# mixer-board3.net
KiCad netlist of a schematic drawn in EAGLE
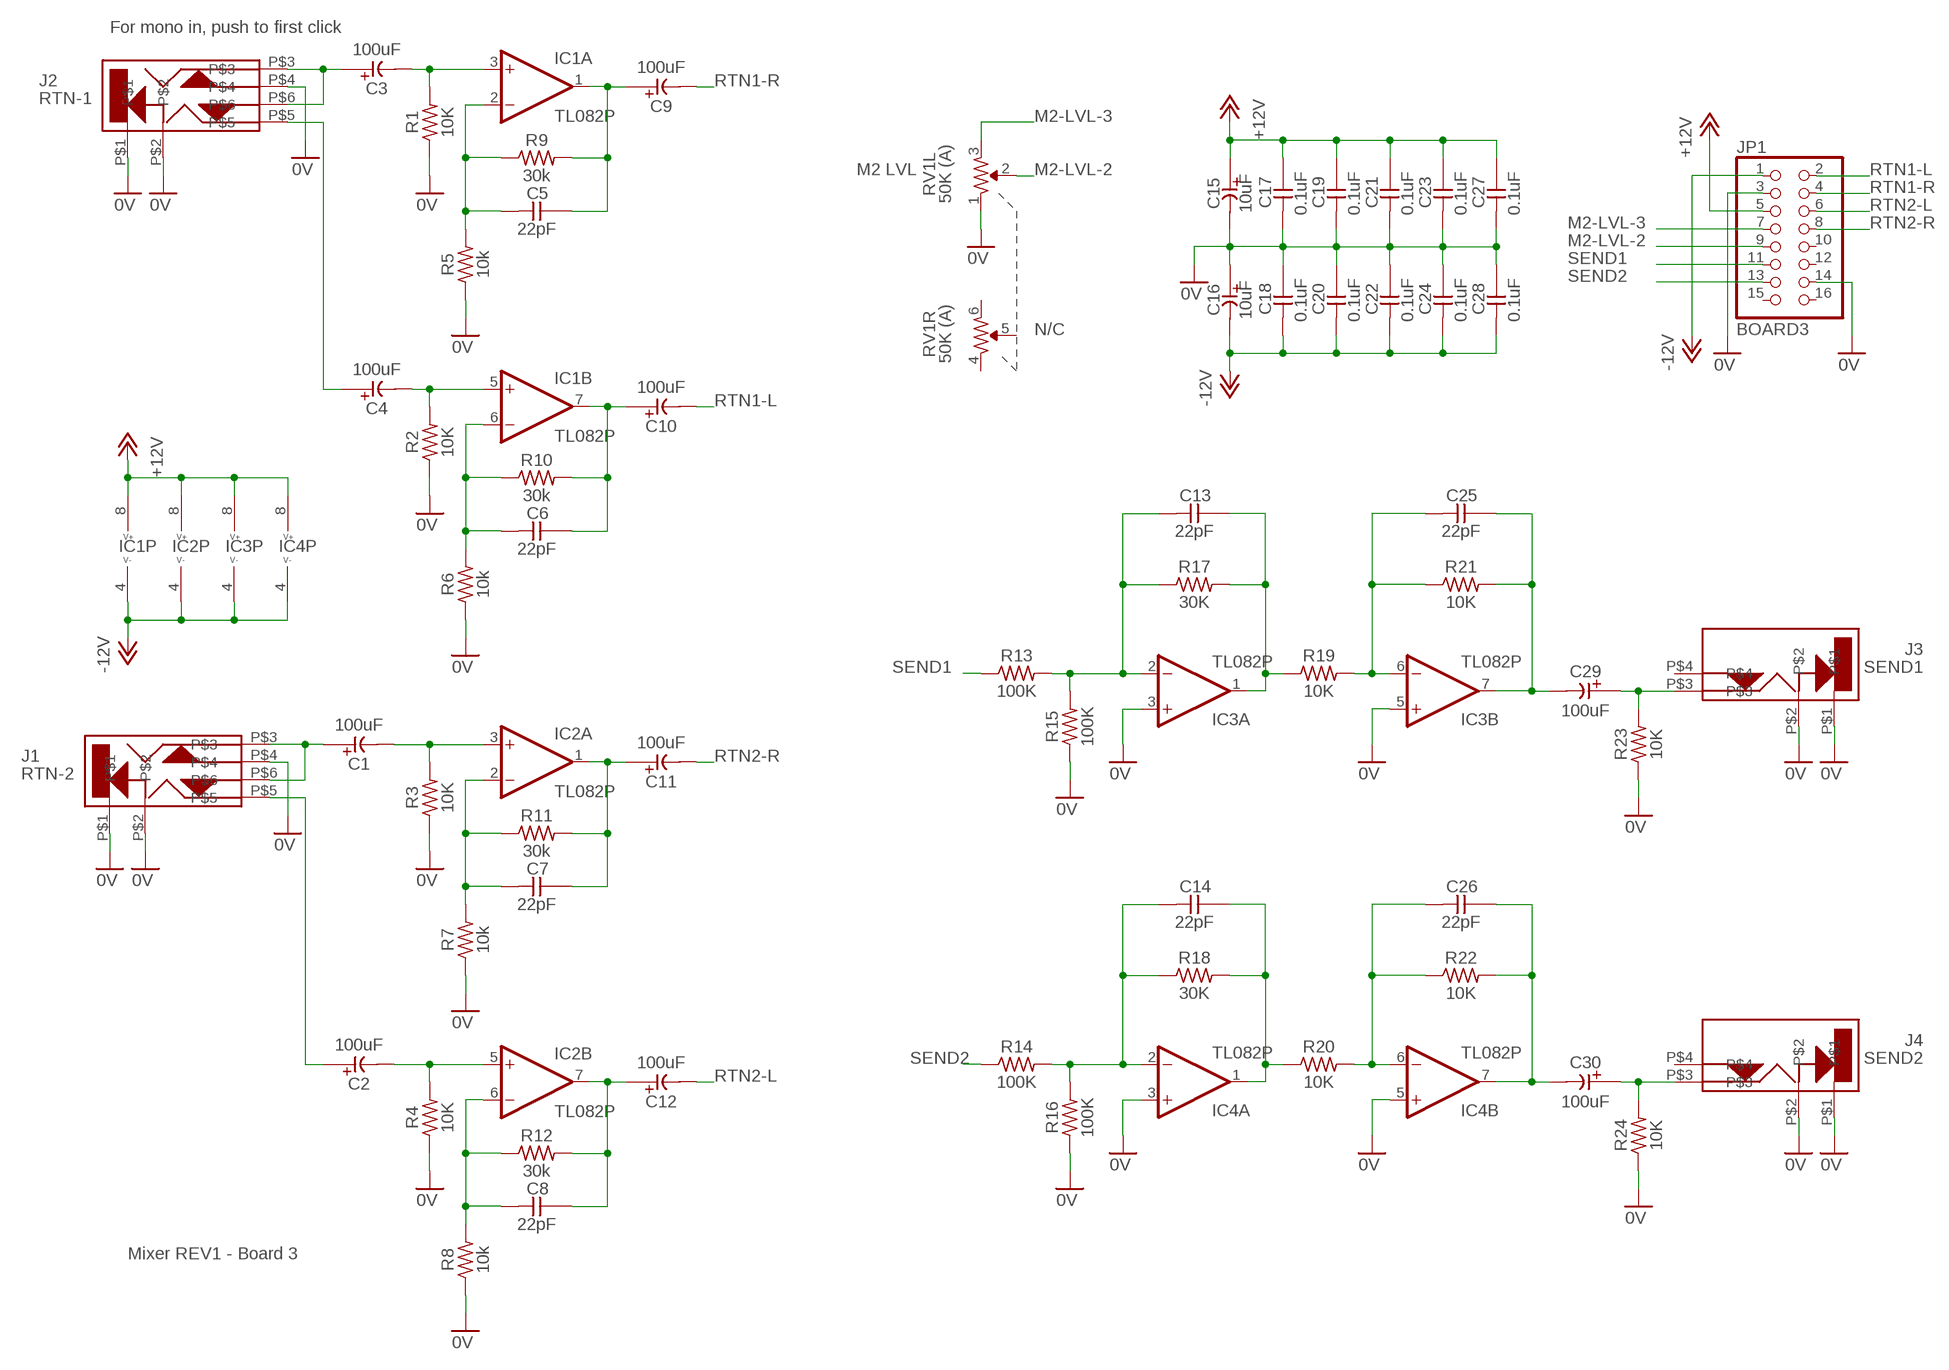
[diagram p0: schematic, sheet 1]

(export (version "E")
  (design (tool "Eeschema 10.0.6"))
  (components
    (comp (ref "C1")
      (value "100uF")
      (footprint "eagle-import:E5-8,5")
      (libsource (lib "eagle-import") (part "CE-USE5-8.5"))
    )
    (comp (ref "C2")
      (value "100uF")
      (footprint "eagle-import:E5-8,5")
      (libsource (lib "eagle-import") (part "CE-USE5-8.5"))
    )
    (comp (ref "C3")
      (value "100uF")
      (footprint "eagle-import:E5-8,5")
      (libsource (lib "eagle-import") (part "CE-USE5-8.5"))
    )
    (comp (ref "C4")
      (value "100uF")
      (footprint "eagle-import:E5-8,5")
      (libsource (lib "eagle-import") (part "CE-USE5-8.5"))
    )
    (comp (ref "C5")
      (value "22pF")
      (footprint "eagle-import:C025-024X044")
      (libsource (lib "eagle-import") (part "CC-US025-024X044"))
    )
    (comp (ref "C6")
      (value "22pF")
      (footprint "eagle-import:C025-024X044")
      (libsource (lib "eagle-import") (part "CC-US025-024X044"))
    )
    (comp (ref "C7")
      (value "22pF")
      (footprint "eagle-import:C025-024X044")
      (libsource (lib "eagle-import") (part "CC-US025-024X044"))
    )
    (comp (ref "C8")
      (value "22pF")
      (footprint "eagle-import:C025-024X044")
      (libsource (lib "eagle-import") (part "CC-US025-024X044"))
    )
    (comp (ref "C9")
      (value "100uF")
      (footprint "eagle-import:E5-8,5")
      (libsource (lib "eagle-import") (part "CE-USE5-8.5"))
    )
    (comp (ref "C10")
      (value "100uF")
      (footprint "eagle-import:E5-8,5")
      (libsource (lib "eagle-import") (part "CE-USE5-8.5"))
    )
    (comp (ref "C11")
      (value "100uF")
      (footprint "eagle-import:E5-8,5")
      (libsource (lib "eagle-import") (part "CE-USE5-8.5"))
    )
    (comp (ref "C12")
      (value "100uF")
      (footprint "eagle-import:E5-8,5")
      (libsource (lib "eagle-import") (part "CE-USE5-8.5"))
    )
    (comp (ref "C13")
      (value "22pF")
      (footprint "eagle-import:C025-024X044")
      (libsource (lib "eagle-import") (part "CC-US025-024X044"))
    )
    (comp (ref "C14")
      (value "22pF")
      (footprint "eagle-import:C025-024X044")
      (libsource (lib "eagle-import") (part "CC-US025-024X044"))
    )
    (comp (ref "C15")
      (value "10uF")
      (footprint "eagle-import:E2-5")
      (libsource (lib "eagle-import") (part "_common.v1_CE-USE2-5"))
    )
    (comp (ref "C16")
      (value "10uF")
      (footprint "eagle-import:E2-5")
      (libsource (lib "eagle-import") (part "_common.v1_CE-USE2-5"))
    )
    (comp (ref "C17")
      (value "0.1uF")
      (footprint "eagle-import:C025-024X044")
      (libsource (lib "eagle-import") (part "_common.v1_CC-US025-024X044"))
    )
    (comp (ref "C18")
      (value "0.1uF")
      (footprint "eagle-import:C025-024X044")
      (libsource (lib "eagle-import") (part "_common.v1_CC-US025-024X044"))
    )
    (comp (ref "C19")
      (value "0.1uF")
      (footprint "eagle-import:C025-024X044")
      (libsource (lib "eagle-import") (part "_common.v1_CC-US025-024X044"))
    )
    (comp (ref "C20")
      (value "0.1uF")
      (footprint "eagle-import:C025-024X044")
      (libsource (lib "eagle-import") (part "_common.v1_CC-US025-024X044"))
    )
    (comp (ref "C21")
      (value "0.1uF")
      (footprint "eagle-import:C025-024X044")
      (libsource (lib "eagle-import") (part "_common.v1_CC-US025-024X044"))
    )
    (comp (ref "C22")
      (value "0.1uF")
      (footprint "eagle-import:C025-024X044")
      (libsource (lib "eagle-import") (part "_common.v1_CC-US025-024X044"))
    )
    (comp (ref "C23")
      (value "0.1uF")
      (footprint "eagle-import:C025-024X044")
      (libsource (lib "eagle-import") (part "_common.v1_CC-US025-024X044"))
    )
    (comp (ref "C24")
      (value "0.1uF")
      (footprint "eagle-import:C025-024X044")
      (libsource (lib "eagle-import") (part "_common.v1_CC-US025-024X044"))
    )
    (comp (ref "C25")
      (value "22pF")
      (footprint "eagle-import:C025-024X044")
      (libsource (lib "eagle-import") (part "CC-US025-024X044"))
    )
    (comp (ref "C26")
      (value "22pF")
      (footprint "eagle-import:C025-024X044")
      (libsource (lib "eagle-import") (part "CC-US025-024X044"))
    )
    (comp (ref "C27")
      (value "0.1uF")
      (footprint "eagle-import:C025-024X044")
      (libsource (lib "eagle-import") (part "_common.v1_CC-US025-024X044"))
    )
    (comp (ref "C28")
      (value "0.1uF")
      (footprint "eagle-import:C025-024X044")
      (libsource (lib "eagle-import") (part "_common.v1_CC-US025-024X044"))
    )
    (comp (ref "C29")
      (value "100uF")
      (footprint "eagle-import:E5-8,5")
      (libsource (lib "eagle-import") (part "CE-USE5-8.5"))
    )
    (comp (ref "C30")
      (value "100uF")
      (footprint "eagle-import:E5-8,5")
      (libsource (lib "eagle-import") (part "CE-USE5-8.5"))
    )
    (comp (ref "IC1")
      (value "TL082P")
      (footprint "eagle-import:DIL08")
      (libsource (lib "eagle-import") (part "TL082P"))
    )
    (comp (ref "IC2")
      (value "TL082P")
      (footprint "eagle-import:DIL08")
      (libsource (lib "eagle-import") (part "TL082P"))
    )
    (comp (ref "IC3")
      (value "TL082P")
      (footprint "eagle-import:DIL08")
      (libsource (lib "eagle-import") (part "TL082P"))
    )
    (comp (ref "IC4")
      (value "TL082P")
      (footprint "eagle-import:DIL08")
      (libsource (lib "eagle-import") (part "TL082P"))
    )
    (comp (ref "J1")
      (value "RTN-2")
      (footprint "eagle-import:NYS216-U")
      (libsource (lib "eagle-import") (part "NYS216-U"))
    )
    (comp (ref "J2")
      (value "RTN-1")
      (footprint "eagle-import:NYS216-U")
      (libsource (lib "eagle-import") (part "NYS216-U"))
    )
    (comp (ref "J3")
      (value "SEND1")
      (footprint "eagle-import:NYS2162-U")
      (libsource (lib "eagle-import") (part "NYS2162-U"))
    )
    (comp (ref "J4")
      (value "SEND2")
      (footprint "eagle-import:NYS2162-U")
      (libsource (lib "eagle-import") (part "NYS2162-U"))
    )
    (comp (ref "JP1")
      (value "BOARD3")
      (footprint "eagle-import:2X08")
      (libsource (lib "eagle-import") (part "PINHD-2X8"))
    )
    (comp (ref "R1")
      (value "10K")
      (footprint "eagle-import:0207_7")
      (libsource (lib "eagle-import") (part "R"))
    )
    (comp (ref "R2")
      (value "10K")
      (footprint "eagle-import:0207_7")
      (libsource (lib "eagle-import") (part "R"))
    )
    (comp (ref "R3")
      (value "10K")
      (footprint "eagle-import:0207_7")
      (libsource (lib "eagle-import") (part "R"))
    )
    (comp (ref "R4")
      (value "10K")
      (footprint "eagle-import:0207_7")
      (libsource (lib "eagle-import") (part "R"))
    )
    (comp (ref "R5")
      (value "10k")
      (footprint "eagle-import:0207_7")
      (libsource (lib "eagle-import") (part "R"))
    )
    (comp (ref "R6")
      (value "10k")
      (footprint "eagle-import:0207_7")
      (libsource (lib "eagle-import") (part "R"))
    )
    (comp (ref "R7")
      (value "10k")
      (footprint "eagle-import:0207_7")
      (libsource (lib "eagle-import") (part "R"))
    )
    (comp (ref "R8")
      (value "10k")
      (footprint "eagle-import:0207_7")
      (libsource (lib "eagle-import") (part "R"))
    )
    (comp (ref "R9")
      (value "30k")
      (footprint "eagle-import:0207_7")
      (libsource (lib "eagle-import") (part "R"))
    )
    (comp (ref "R10")
      (value "30k")
      (footprint "eagle-import:0207_7")
      (libsource (lib "eagle-import") (part "R"))
    )
    (comp (ref "R11")
      (value "30k")
      (footprint "eagle-import:0207_7")
      (libsource (lib "eagle-import") (part "R"))
    )
    (comp (ref "R12")
      (value "30k")
      (footprint "eagle-import:0207_7")
      (libsource (lib "eagle-import") (part "R"))
    )
    (comp (ref "R13")
      (value "100K")
      (footprint "eagle-import:0207_7")
      (libsource (lib "eagle-import") (part "R"))
    )
    (comp (ref "R14")
      (value "100K")
      (footprint "eagle-import:0207_7")
      (libsource (lib "eagle-import") (part "R"))
    )
    (comp (ref "R15")
      (value "100K")
      (footprint "eagle-import:0207_7")
      (libsource (lib "eagle-import") (part "R"))
    )
    (comp (ref "R16")
      (value "100K")
      (footprint "eagle-import:0207_7")
      (libsource (lib "eagle-import") (part "R"))
    )
    (comp (ref "R17")
      (value "30K")
      (footprint "eagle-import:0207_7")
      (libsource (lib "eagle-import") (part "R"))
    )
    (comp (ref "R18")
      (value "30K")
      (footprint "eagle-import:0207_7")
      (libsource (lib "eagle-import") (part "R"))
    )
    (comp (ref "R19")
      (value "10K")
      (footprint "eagle-import:0207_7")
      (libsource (lib "eagle-import") (part "R"))
    )
    (comp (ref "R20")
      (value "10K")
      (footprint "eagle-import:0207_7")
      (libsource (lib "eagle-import") (part "R"))
    )
    (comp (ref "R21")
      (value "10K")
      (footprint "eagle-import:0207_7")
      (libsource (lib "eagle-import") (part "R"))
    )
    (comp (ref "R22")
      (value "10K")
      (footprint "eagle-import:0207_7")
      (libsource (lib "eagle-import") (part "R"))
    )
    (comp (ref "R23")
      (value "10K")
      (footprint "eagle-import:0207_7")
      (libsource (lib "eagle-import") (part "R"))
    )
    (comp (ref "R24")
      (value "10K")
      (footprint "eagle-import:0207_7")
      (libsource (lib "eagle-import") (part "R"))
    )
    (comp (ref "RV1")
      (value "50K (A)")
      (footprint "eagle-import:_COMMON_3RP_1610G")
      (libsource (lib "eagle-import") (part "R-VAR-ST"))
    )
  )
  (nets
    (net (code "1") (name "+12V") (class "Default")
      (node (ref "C15") (pin "+") (pinfunction "+_+") (pintype "passive"))
      (node (ref "C17") (pin "1") (pinfunction "1_1") (pintype "passive"))
      (node (ref "C19") (pin "1") (pinfunction "1_1") (pintype "passive"))
      (node (ref "C21") (pin "1") (pinfunction "1_1") (pintype "passive"))
      (node (ref "C23") (pin "1") (pinfunction "1_1") (pintype "passive"))
      (node (ref "C27") (pin "1") (pinfunction "1_1") (pintype "passive"))
      (node (ref "IC1") (pin "8") (pinfunction "V+_8") (pintype "power_in"))
      (node (ref "IC2") (pin "8") (pinfunction "V+_8") (pintype "power_in"))
      (node (ref "IC3") (pin "8") (pinfunction "V+_8") (pintype "power_in"))
      (node (ref "IC4") (pin "8") (pinfunction "V+_8") (pintype "power_in"))
      (node (ref "JP1") (pin "5") (pinfunction "5_5") (pintype "passive"))
    )
    (net (code "2") (name "-12V") (class "Default")
      (node (ref "C16") (pin "-") (pinfunction "-_-") (pintype "passive"))
      (node (ref "C18") (pin "2") (pinfunction "2_2") (pintype "passive"))
      (node (ref "C20") (pin "2") (pinfunction "2_2") (pintype "passive"))
      (node (ref "C22") (pin "2") (pinfunction "2_2") (pintype "passive"))
      (node (ref "C24") (pin "2") (pinfunction "2_2") (pintype "passive"))
      (node (ref "C28") (pin "2") (pinfunction "2_2") (pintype "passive"))
      (node (ref "IC1") (pin "4") (pinfunction "V-_4") (pintype "power_in"))
      (node (ref "IC2") (pin "4") (pinfunction "V-_4") (pintype "power_in"))
      (node (ref "IC3") (pin "4") (pinfunction "V-_4") (pintype "power_in"))
      (node (ref "IC4") (pin "4") (pinfunction "V-_4") (pintype "power_in"))
      (node (ref "JP1") (pin "1") (pinfunction "1_1") (pintype "passive"))
    )
    (net (code "3") (name "/M2-LVL-2") (class "Default")
      (node (ref "JP1") (pin "9") (pinfunction "9_9") (pintype "passive"))
      (node (ref "RV1") (pin "2") (pinfunction "2_2") (pintype "passive"))
    )
    (net (code "4") (name "/M2-LVL-3") (class "Default")
      (node (ref "JP1") (pin "7") (pinfunction "7_7") (pintype "passive"))
      (node (ref "RV1") (pin "3") (pinfunction "3_3") (pintype "passive"))
    )
    (net (code "5") (name "/RTN1-L") (class "Default")
      (node (ref "C10") (pin "-") (pinfunction "-_-") (pintype "passive"))
      (node (ref "JP1") (pin "2") (pinfunction "2_2") (pintype "passive"))
    )
    (net (code "6") (name "/RTN1-R") (class "Default")
      (node (ref "C9") (pin "-") (pinfunction "-_-") (pintype "passive"))
      (node (ref "JP1") (pin "4") (pinfunction "4_4") (pintype "passive"))
    )
    (net (code "7") (name "/RTN2-L") (class "Default")
      (node (ref "C12") (pin "-") (pinfunction "-_-") (pintype "passive"))
      (node (ref "JP1") (pin "6") (pinfunction "6_6") (pintype "passive"))
    )
    (net (code "8") (name "/RTN2-R") (class "Default")
      (node (ref "C11") (pin "-") (pinfunction "-_-") (pintype "passive"))
      (node (ref "JP1") (pin "8") (pinfunction "8_8") (pintype "passive"))
    )
    (net (code "9") (name "/SEND1") (class "Default")
      (node (ref "JP1") (pin "11") (pinfunction "11_11") (pintype "passive"))
      (node (ref "R13") (pin "1") (pinfunction "1_1") (pintype "passive"))
    )
    (net (code "10") (name "/SEND2") (class "Default")
      (node (ref "JP1") (pin "13") (pinfunction "13_13") (pintype "passive"))
      (node (ref "R14") (pin "1") (pinfunction "1_1") (pintype "passive"))
    )
    (net (code "11") (name "0V") (class "Default")
      (node (ref "C15") (pin "-") (pinfunction "-_-") (pintype "passive"))
      (node (ref "C16") (pin "+") (pinfunction "+_+") (pintype "passive"))
      (node (ref "C17") (pin "2") (pinfunction "2_2") (pintype "passive"))
      (node (ref "C18") (pin "1") (pinfunction "1_1") (pintype "passive"))
      (node (ref "C19") (pin "2") (pinfunction "2_2") (pintype "passive"))
      (node (ref "C20") (pin "1") (pinfunction "1_1") (pintype "passive"))
      (node (ref "C21") (pin "2") (pinfunction "2_2") (pintype "passive"))
      (node (ref "C22") (pin "1") (pinfunction "1_1") (pintype "passive"))
      (node (ref "C23") (pin "2") (pinfunction "2_2") (pintype "passive"))
      (node (ref "C24") (pin "1") (pinfunction "1_1") (pintype "passive"))
      (node (ref "C27") (pin "2") (pinfunction "2_2") (pintype "passive"))
      (node (ref "C28") (pin "1") (pinfunction "1_1") (pintype "passive"))
      (node (ref "IC3") (pin "3") (pinfunction "+IN_3") (pintype "input"))
      (node (ref "IC3") (pin "5") (pinfunction "+IN_5") (pintype "input"))
      (node (ref "IC4") (pin "3") (pinfunction "+IN_3") (pintype "input"))
      (node (ref "IC4") (pin "5") (pinfunction "+IN_5") (pintype "input"))
      (node (ref "J1") (pin "P$1") (pinfunction "P$1_P$1") (pintype "bidirectional"))
      (node (ref "J1") (pin "P$2") (pinfunction "P$2_P$2") (pintype "bidirectional"))
      (node (ref "J1") (pin "P$4") (pinfunction "P$4_P$4") (pintype "bidirectional"))
      (node (ref "J2") (pin "P$1") (pinfunction "P$1_P$1") (pintype "bidirectional"))
      (node (ref "J2") (pin "P$2") (pinfunction "P$2_P$2") (pintype "bidirectional"))
      (node (ref "J2") (pin "P$4") (pinfunction "P$4_P$4") (pintype "bidirectional"))
      (node (ref "J3") (pin "P$1") (pinfunction "P$1_P$1") (pintype "bidirectional"))
      (node (ref "J3") (pin "P$2") (pinfunction "P$2_P$2") (pintype "bidirectional"))
      (node (ref "J4") (pin "P$1") (pinfunction "P$1_P$1") (pintype "bidirectional"))
      (node (ref "J4") (pin "P$2") (pinfunction "P$2_P$2") (pintype "bidirectional"))
      (node (ref "JP1") (pin "14") (pinfunction "14_14") (pintype "passive"))
      (node (ref "JP1") (pin "3") (pinfunction "3_3") (pintype "passive"))
      (node (ref "R1") (pin "1") (pinfunction "1_1") (pintype "passive"))
      (node (ref "R15") (pin "1") (pinfunction "1_1") (pintype "passive"))
      (node (ref "R16") (pin "1") (pinfunction "1_1") (pintype "passive"))
      (node (ref "R2") (pin "1") (pinfunction "1_1") (pintype "passive"))
      (node (ref "R23") (pin "1") (pinfunction "1_1") (pintype "passive"))
      (node (ref "R24") (pin "1") (pinfunction "1_1") (pintype "passive"))
      (node (ref "R3") (pin "1") (pinfunction "1_1") (pintype "passive"))
      (node (ref "R4") (pin "1") (pinfunction "1_1") (pintype "passive"))
      (node (ref "R5") (pin "1") (pinfunction "1_1") (pintype "passive"))
      (node (ref "R6") (pin "1") (pinfunction "1_1") (pintype "passive"))
      (node (ref "R7") (pin "1") (pinfunction "1_1") (pintype "passive"))
      (node (ref "R8") (pin "1") (pinfunction "1_1") (pintype "passive"))
      (node (ref "RV1") (pin "1") (pinfunction "1_1") (pintype "passive"))
    )
    (net (code "12") (name "Net-(C1-Pad+)") (class "Default")
      (node (ref "C1") (pin "+") (pinfunction "+_+") (pintype "passive"))
      (node (ref "J1") (pin "P$3") (pinfunction "P$3_P$3") (pintype "bidirectional"))
      (node (ref "J1") (pin "P$6") (pinfunction "P$6_P$6") (pintype "bidirectional"))
    )
    (net (code "13") (name "Net-(C2-Pad+)") (class "Default")
      (node (ref "C2") (pin "+") (pinfunction "+_+") (pintype "passive"))
      (node (ref "J1") (pin "P$5") (pinfunction "P$5_P$5") (pintype "bidirectional"))
    )
    (net (code "14") (name "Net-(C3-Pad+)") (class "Default")
      (node (ref "C3") (pin "+") (pinfunction "+_+") (pintype "passive"))
      (node (ref "J2") (pin "P$3") (pinfunction "P$3_P$3") (pintype "bidirectional"))
      (node (ref "J2") (pin "P$6") (pinfunction "P$6_P$6") (pintype "bidirectional"))
    )
    (net (code "15") (name "Net-(C4-Pad+)") (class "Default")
      (node (ref "C4") (pin "+") (pinfunction "+_+") (pintype "passive"))
      (node (ref "J2") (pin "P$5") (pinfunction "P$5_P$5") (pintype "bidirectional"))
    )
    (net (code "16") (name "Net-(C29-Pad+)") (class "Default")
      (node (ref "C29") (pin "+") (pinfunction "+_+") (pintype "passive"))
      (node (ref "J3") (pin "P$3") (pinfunction "P$3_P$3") (pintype "bidirectional"))
      (node (ref "R23") (pin "2") (pinfunction "2_2") (pintype "passive"))
    )
    (net (code "17") (name "Net-(C30-Pad+)") (class "Default")
      (node (ref "C30") (pin "+") (pinfunction "+_+") (pintype "passive"))
      (node (ref "J4") (pin "P$3") (pinfunction "P$3_P$3") (pintype "bidirectional"))
      (node (ref "R24") (pin "2") (pinfunction "2_2") (pintype "passive"))
    )
    (net (code "18") (name "Net-(IC1A-+IN)") (class "Default")
      (node (ref "C3") (pin "-") (pinfunction "-_-") (pintype "passive"))
      (node (ref "IC1") (pin "3") (pinfunction "+IN_3") (pintype "input"))
      (node (ref "R1") (pin "2") (pinfunction "2_2") (pintype "passive"))
    )
    (net (code "19") (name "Net-(IC1A--IN)") (class "Default")
      (node (ref "C5") (pin "2") (pinfunction "2_2") (pintype "passive"))
      (node (ref "IC1") (pin "2") (pinfunction "-IN_2") (pintype "input"))
      (node (ref "R5") (pin "2") (pinfunction "2_2") (pintype "passive"))
      (node (ref "R9") (pin "1") (pinfunction "1_1") (pintype "passive"))
    )
    (net (code "20") (name "Net-(IC1A-OUT)") (class "Default")
      (node (ref "C5") (pin "1") (pinfunction "1_1") (pintype "passive"))
      (node (ref "C9") (pin "+") (pinfunction "+_+") (pintype "passive"))
      (node (ref "IC1") (pin "1") (pinfunction "OUT_1") (pintype "output"))
      (node (ref "R9") (pin "2") (pinfunction "2_2") (pintype "passive"))
    )
    (net (code "21") (name "Net-(IC1B-+IN)") (class "Default")
      (node (ref "C4") (pin "-") (pinfunction "-_-") (pintype "passive"))
      (node (ref "IC1") (pin "5") (pinfunction "+IN_5") (pintype "input"))
      (node (ref "R2") (pin "2") (pinfunction "2_2") (pintype "passive"))
    )
    (net (code "22") (name "Net-(IC1B--IN)") (class "Default")
      (node (ref "C6") (pin "2") (pinfunction "2_2") (pintype "passive"))
      (node (ref "IC1") (pin "6") (pinfunction "-IN_6") (pintype "input"))
      (node (ref "R10") (pin "1") (pinfunction "1_1") (pintype "passive"))
      (node (ref "R6") (pin "2") (pinfunction "2_2") (pintype "passive"))
    )
    (net (code "23") (name "Net-(IC1B-OUT)") (class "Default")
      (node (ref "C10") (pin "+") (pinfunction "+_+") (pintype "passive"))
      (node (ref "C6") (pin "1") (pinfunction "1_1") (pintype "passive"))
      (node (ref "IC1") (pin "7") (pinfunction "OUT_7") (pintype "output"))
      (node (ref "R10") (pin "2") (pinfunction "2_2") (pintype "passive"))
    )
    (net (code "24") (name "Net-(IC2A-+IN)") (class "Default")
      (node (ref "C1") (pin "-") (pinfunction "-_-") (pintype "passive"))
      (node (ref "IC2") (pin "3") (pinfunction "+IN_3") (pintype "input"))
      (node (ref "R3") (pin "2") (pinfunction "2_2") (pintype "passive"))
    )
    (net (code "25") (name "Net-(IC2A--IN)") (class "Default")
      (node (ref "C7") (pin "2") (pinfunction "2_2") (pintype "passive"))
      (node (ref "IC2") (pin "2") (pinfunction "-IN_2") (pintype "input"))
      (node (ref "R11") (pin "1") (pinfunction "1_1") (pintype "passive"))
      (node (ref "R7") (pin "2") (pinfunction "2_2") (pintype "passive"))
    )
    (net (code "26") (name "Net-(IC2A-OUT)") (class "Default")
      (node (ref "C11") (pin "+") (pinfunction "+_+") (pintype "passive"))
      (node (ref "C7") (pin "1") (pinfunction "1_1") (pintype "passive"))
      (node (ref "IC2") (pin "1") (pinfunction "OUT_1") (pintype "output"))
      (node (ref "R11") (pin "2") (pinfunction "2_2") (pintype "passive"))
    )
    (net (code "27") (name "Net-(IC2B-+IN)") (class "Default")
      (node (ref "C2") (pin "-") (pinfunction "-_-") (pintype "passive"))
      (node (ref "IC2") (pin "5") (pinfunction "+IN_5") (pintype "input"))
      (node (ref "R4") (pin "2") (pinfunction "2_2") (pintype "passive"))
    )
    (net (code "28") (name "Net-(IC2B--IN)") (class "Default")
      (node (ref "C8") (pin "2") (pinfunction "2_2") (pintype "passive"))
      (node (ref "IC2") (pin "6") (pinfunction "-IN_6") (pintype "input"))
      (node (ref "R12") (pin "1") (pinfunction "1_1") (pintype "passive"))
      (node (ref "R8") (pin "2") (pinfunction "2_2") (pintype "passive"))
    )
    (net (code "29") (name "Net-(IC2B-OUT)") (class "Default")
      (node (ref "C12") (pin "+") (pinfunction "+_+") (pintype "passive"))
      (node (ref "C8") (pin "1") (pinfunction "1_1") (pintype "passive"))
      (node (ref "IC2") (pin "7") (pinfunction "OUT_7") (pintype "output"))
      (node (ref "R12") (pin "2") (pinfunction "2_2") (pintype "passive"))
    )
    (net (code "30") (name "Net-(IC3A--IN)") (class "Default")
      (node (ref "C13") (pin "2") (pinfunction "2_2") (pintype "passive"))
      (node (ref "IC3") (pin "2") (pinfunction "-IN_2") (pintype "input"))
      (node (ref "R13") (pin "2") (pinfunction "2_2") (pintype "passive"))
      (node (ref "R15") (pin "2") (pinfunction "2_2") (pintype "passive"))
      (node (ref "R17") (pin "1") (pinfunction "1_1") (pintype "passive"))
    )
    (net (code "31") (name "Net-(IC3A-OUT)") (class "Default")
      (node (ref "C13") (pin "1") (pinfunction "1_1") (pintype "passive"))
      (node (ref "IC3") (pin "1") (pinfunction "OUT_1") (pintype "output"))
      (node (ref "R17") (pin "2") (pinfunction "2_2") (pintype "passive"))
      (node (ref "R19") (pin "1") (pinfunction "1_1") (pintype "passive"))
    )
    (net (code "32") (name "Net-(IC3B--IN)") (class "Default")
      (node (ref "C25") (pin "2") (pinfunction "2_2") (pintype "passive"))
      (node (ref "IC3") (pin "6") (pinfunction "-IN_6") (pintype "input"))
      (node (ref "R19") (pin "2") (pinfunction "2_2") (pintype "passive"))
      (node (ref "R21") (pin "1") (pinfunction "1_1") (pintype "passive"))
    )
    (net (code "33") (name "Net-(IC3B-OUT)") (class "Default")
      (node (ref "C25") (pin "1") (pinfunction "1_1") (pintype "passive"))
      (node (ref "C29") (pin "-") (pinfunction "-_-") (pintype "passive"))
      (node (ref "IC3") (pin "7") (pinfunction "OUT_7") (pintype "output"))
      (node (ref "R21") (pin "2") (pinfunction "2_2") (pintype "passive"))
    )
    (net (code "34") (name "Net-(IC4A--IN)") (class "Default")
      (node (ref "C14") (pin "2") (pinfunction "2_2") (pintype "passive"))
      (node (ref "IC4") (pin "2") (pinfunction "-IN_2") (pintype "input"))
      (node (ref "R14") (pin "2") (pinfunction "2_2") (pintype "passive"))
      (node (ref "R16") (pin "2") (pinfunction "2_2") (pintype "passive"))
      (node (ref "R18") (pin "1") (pinfunction "1_1") (pintype "passive"))
    )
    (net (code "35") (name "Net-(IC4A-OUT)") (class "Default")
      (node (ref "C14") (pin "1") (pinfunction "1_1") (pintype "passive"))
      (node (ref "IC4") (pin "1") (pinfunction "OUT_1") (pintype "output"))
      (node (ref "R18") (pin "2") (pinfunction "2_2") (pintype "passive"))
      (node (ref "R20") (pin "1") (pinfunction "1_1") (pintype "passive"))
    )
    (net (code "36") (name "Net-(IC4B--IN)") (class "Default")
      (node (ref "C26") (pin "2") (pinfunction "2_2") (pintype "passive"))
      (node (ref "IC4") (pin "6") (pinfunction "-IN_6") (pintype "input"))
      (node (ref "R20") (pin "2") (pinfunction "2_2") (pintype "passive"))
      (node (ref "R22") (pin "1") (pinfunction "1_1") (pintype "passive"))
    )
    (net (code "37") (name "Net-(IC4B-OUT)") (class "Default")
      (node (ref "C26") (pin "1") (pinfunction "1_1") (pintype "passive"))
      (node (ref "C30") (pin "-") (pinfunction "-_-") (pintype "passive"))
      (node (ref "IC4") (pin "7") (pinfunction "OUT_7") (pintype "output"))
      (node (ref "R22") (pin "2") (pinfunction "2_2") (pintype "passive"))
    )
    (net (code "38") (name "unconnected-(J3-PadP$4)") (class "Default")
      (node (ref "J3") (pin "P$4") (pinfunction "P$4_P$4") (pintype "bidirectional"))
    )
    (net (code "39") (name "unconnected-(J4-PadP$4)") (class "Default")
      (node (ref "J4") (pin "P$4") (pinfunction "P$4_P$4") (pintype "bidirectional"))
    )
    (net (code "40") (name "unconnected-(JP1-Pad10)") (class "Default")
      (node (ref "JP1") (pin "10") (pinfunction "10_10") (pintype "passive"))
    )
    (net (code "41") (name "unconnected-(JP1-Pad12)") (class "Default")
      (node (ref "JP1") (pin "12") (pinfunction "12_12") (pintype "passive"))
    )
    (net (code "42") (name "unconnected-(JP1-Pad15)") (class "Default")
      (node (ref "JP1") (pin "15") (pinfunction "15_15") (pintype "passive"))
    )
    (net (code "43") (name "unconnected-(JP1-Pad16)") (class "Default")
      (node (ref "JP1") (pin "16") (pinfunction "16_16") (pintype "passive"))
    )
    (net (code "44") (name "unconnected-(RV1B-1-Pad4)") (class "Default")
      (node (ref "RV1") (pin "4") (pinfunction "1_4") (pintype "passive"))
    )
    (net (code "45") (name "unconnected-(RV1B-2-Pad5)") (class "Default")
      (node (ref "RV1") (pin "5") (pinfunction "2_5") (pintype "passive"))
    )
    (net (code "46") (name "unconnected-(RV1B-3-Pad6)") (class "Default")
      (node (ref "RV1") (pin "6") (pinfunction "3_6") (pintype "passive"))
    )
  )
)
